# DevBit-ATmega328.net
KiCad netlist of a schematic drawn in EAGLE
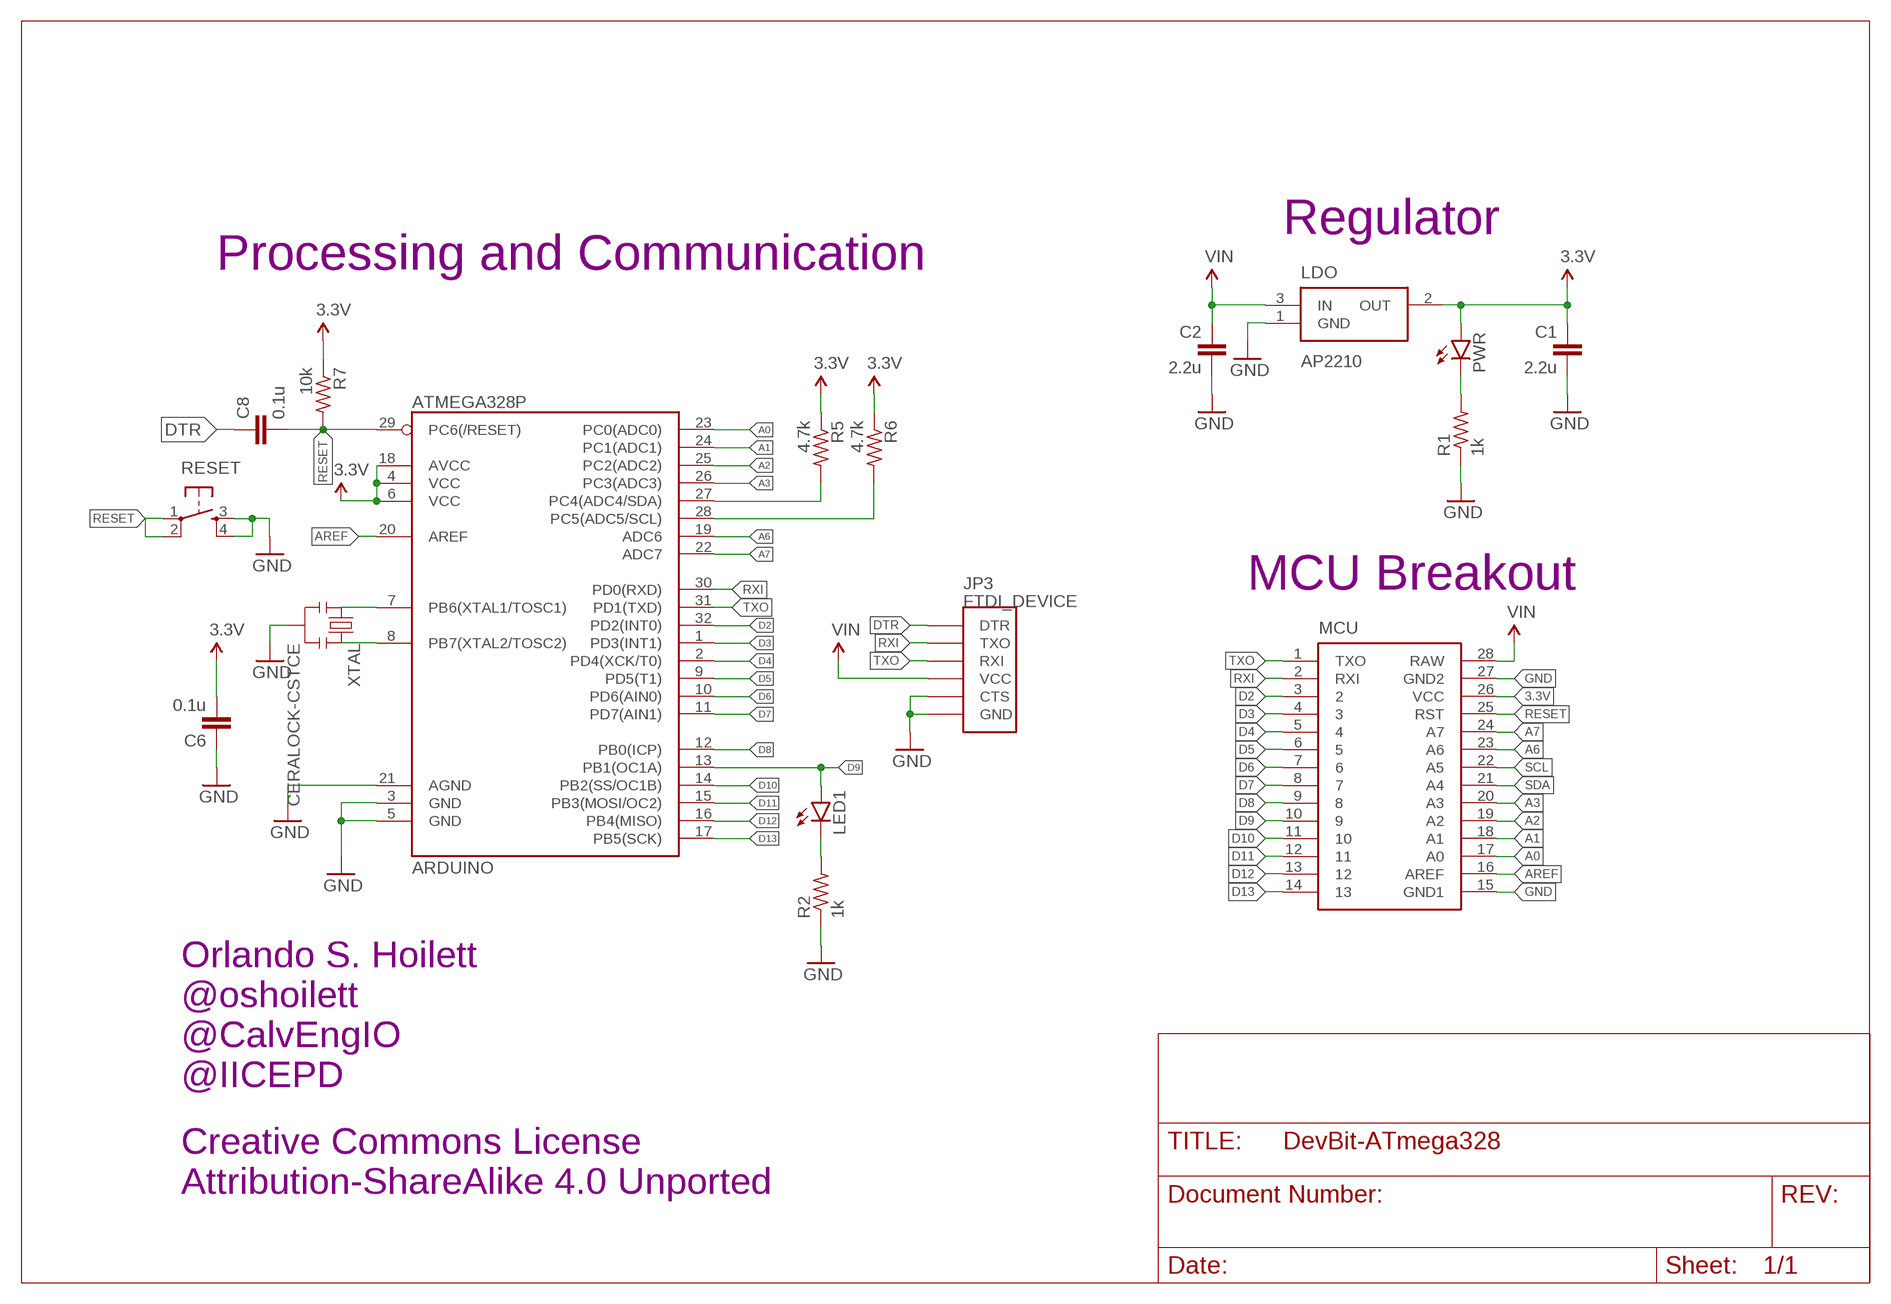
[diagram p0: schematic, sheet 1]

(export (version "E")
  (design (tool "Eeschema 10.0.6"))
  (components
    (comp (ref "ARDUINO")
      (value "ATMEGA328P")
      (footprint "eagle-import:TQFP32-08")
      (libsource (lib "eagle-import") (part "ATMEGA328_SMT-OHMOD"))
    )
    (comp (ref "C1")
      (value "2.2u")
      (footprint "eagle-import:C0402")
      (libsource (lib "eagle-import") (part "C-EUC0402"))
    )
    (comp (ref "C2")
      (value "2.2u")
      (footprint "eagle-import:C0402")
      (libsource (lib "eagle-import") (part "C-EUC0402"))
    )
    (comp (ref "C6")
      (value "0.1u")
      (footprint "eagle-import:C0402")
      (libsource (lib "eagle-import") (part "C-EUC0402"))
    )
    (comp (ref "C8")
      (value "0.1u")
      (footprint "eagle-import:C0402")
      (libsource (lib "eagle-import") (part "C-EUC0402"))
    )
    (comp (ref "JP3")
      (value "FTDI_DEVICE")
      (footprint "eagle-import:FTDI_DEVICE")
      (libsource (lib "eagle-import") (part "FTDI_DEVICE"))
    )
    (comp (ref "LDO")
      (value "AP2210")
      (footprint "eagle-import:SOT23")
      (libsource (lib "eagle-import") (part "AP2210"))
    )
    (comp (ref "LED1")
      (value "LED0603")
      (footprint "eagle-import:LED-0603")
      (libsource (lib "eagle-import") (part "LED0603"))
    )
    (comp (ref "MCU")
      (value "DEVBASIC-V1")
      (footprint "eagle-import:DEVBIT-BASIC-V1")
      (libsource (lib "eagle-import") (part "DEVBASIC-V1"))
    )
    (comp (ref "PWR")
      (value "LED0603")
      (footprint "eagle-import:LED-0603")
      (libsource (lib "eagle-import") (part "LED0603"))
    )
    (comp (ref "R1")
      (value "1k")
      (footprint "eagle-import:R0402")
      (libsource (lib "eagle-import") (part "R-US_R0402"))
    )
    (comp (ref "R2")
      (value "1k")
      (footprint "eagle-import:R0402")
      (libsource (lib "eagle-import") (part "R-US_R0402"))
    )
    (comp (ref "R5")
      (value "4.7k")
      (footprint "eagle-import:R0402")
      (libsource (lib "eagle-import") (part "R-US_R0402"))
    )
    (comp (ref "R6")
      (value "4.7k")
      (footprint "eagle-import:R0402")
      (libsource (lib "eagle-import") (part "R-US_R0402"))
    )
    (comp (ref "R7")
      (value "10k")
      (footprint "eagle-import:R0402")
      (libsource (lib "eagle-import") (part "R-US_R0402"))
    )
    (comp (ref "RESET")
      (value "BUTTON-PTS830GG140")
      (footprint "eagle-import:BUTTON-GULLWING")
      (libsource (lib "eagle-import") (part "BUTTON-PTS830GG140"))
    )
    (comp (ref "XTAL")
      (value "CERALOCK-CSTCE")
      (footprint "eagle-import:RESONATOR-00")
      (libsource (lib "eagle-import") (part "CERALOCK-CSTCE"))
    )
  )
  (nets
    (net (code "1") (name "3.3V") (class "Default")
      (node (ref "ARDUINO") (pin "18") (pinfunction "AVCC_18") (pintype "bidirectional"))
      (node (ref "ARDUINO") (pin "4") (pinfunction "VCC_4") (pintype "bidirectional"))
      (node (ref "ARDUINO") (pin "6") (pinfunction "VCC_6") (pintype "bidirectional"))
      (node (ref "C1") (pin "1") (pinfunction "1_1") (pintype "passive"))
      (node (ref "C6") (pin "2") (pinfunction "2_2") (pintype "passive"))
      (node (ref "LDO") (pin "2") (pinfunction "OUT_2") (pintype "bidirectional"))
      (node (ref "MCU") (pin "26") (pinfunction "VCC_26") (pintype "bidirectional"))
      (node (ref "PWR") (pin "A") (pinfunction "A_A") (pintype "passive"))
      (node (ref "R5") (pin "1") (pinfunction "1_1") (pintype "passive"))
      (node (ref "R6") (pin "1") (pinfunction "1_1") (pintype "passive"))
      (node (ref "R7") (pin "1") (pinfunction "1_1") (pintype "passive"))
    )
    (net (code "2") (name "A0") (class "Default")
      (node (ref "ARDUINO") (pin "23") (pinfunction "PC0(ADC0)_23") (pintype "bidirectional"))
      (node (ref "MCU") (pin "17") (pinfunction "A0_17") (pintype "bidirectional"))
    )
    (net (code "3") (name "A1") (class "Default")
      (node (ref "ARDUINO") (pin "24") (pinfunction "PC1(ADC1)_24") (pintype "bidirectional"))
      (node (ref "MCU") (pin "18") (pinfunction "A1_18") (pintype "bidirectional"))
    )
    (net (code "4") (name "A2") (class "Default")
      (node (ref "ARDUINO") (pin "25") (pinfunction "PC2(ADC2)_25") (pintype "bidirectional"))
      (node (ref "MCU") (pin "19") (pinfunction "A2_19") (pintype "bidirectional"))
    )
    (net (code "5") (name "A3") (class "Default")
      (node (ref "ARDUINO") (pin "26") (pinfunction "PC3(ADC3)_26") (pintype "bidirectional"))
      (node (ref "MCU") (pin "20") (pinfunction "A3_20") (pintype "bidirectional"))
    )
    (net (code "6") (name "A6") (class "Default")
      (node (ref "ARDUINO") (pin "19") (pinfunction "ADC6_19") (pintype "bidirectional"))
      (node (ref "MCU") (pin "23") (pinfunction "A6_23") (pintype "bidirectional"))
    )
    (net (code "7") (name "A7") (class "Default")
      (node (ref "ARDUINO") (pin "22") (pinfunction "ADC7_22") (pintype "bidirectional"))
      (node (ref "MCU") (pin "24") (pinfunction "A7_24") (pintype "bidirectional"))
    )
    (net (code "8") (name "AREF") (class "Default")
      (node (ref "ARDUINO") (pin "20") (pinfunction "AREF_20") (pintype "bidirectional"))
      (node (ref "MCU") (pin "16") (pinfunction "AREF_16") (pintype "bidirectional"))
    )
    (net (code "9") (name "D2") (class "Default")
      (node (ref "ARDUINO") (pin "32") (pinfunction "PD2(INT0)_32") (pintype "bidirectional"))
      (node (ref "MCU") (pin "3") (pinfunction "2_3") (pintype "bidirectional"))
    )
    (net (code "10") (name "D3") (class "Default")
      (node (ref "ARDUINO") (pin "1") (pinfunction "PD3(INT1)_1") (pintype "bidirectional"))
      (node (ref "MCU") (pin "4") (pinfunction "3_4") (pintype "bidirectional"))
    )
    (net (code "11") (name "D4") (class "Default")
      (node (ref "ARDUINO") (pin "2") (pinfunction "PD4(XCK/T0)_2") (pintype "bidirectional"))
      (node (ref "MCU") (pin "5") (pinfunction "4_5") (pintype "bidirectional"))
    )
    (net (code "12") (name "D5") (class "Default")
      (node (ref "ARDUINO") (pin "9") (pinfunction "PD5(T1)_9") (pintype "bidirectional"))
      (node (ref "MCU") (pin "6") (pinfunction "5_6") (pintype "bidirectional"))
    )
    (net (code "13") (name "D6") (class "Default")
      (node (ref "ARDUINO") (pin "10") (pinfunction "PD6(AIN0)_10") (pintype "bidirectional"))
      (node (ref "MCU") (pin "7") (pinfunction "6_7") (pintype "bidirectional"))
    )
    (net (code "14") (name "D7") (class "Default")
      (node (ref "ARDUINO") (pin "11") (pinfunction "PD7(AIN1)_11") (pintype "bidirectional"))
      (node (ref "MCU") (pin "8") (pinfunction "7_8") (pintype "bidirectional"))
    )
    (net (code "15") (name "D8") (class "Default")
      (node (ref "ARDUINO") (pin "12") (pinfunction "PB0(ICP)_12") (pintype "bidirectional"))
      (node (ref "MCU") (pin "9") (pinfunction "8_9") (pintype "bidirectional"))
    )
    (net (code "16") (name "D9") (class "Default")
      (node (ref "ARDUINO") (pin "13") (pinfunction "PB1(OC1A)_13") (pintype "bidirectional"))
      (node (ref "LED1") (pin "A") (pinfunction "A_A") (pintype "passive"))
      (node (ref "MCU") (pin "10") (pinfunction "9_10") (pintype "bidirectional"))
    )
    (net (code "17") (name "D10") (class "Default")
      (node (ref "ARDUINO") (pin "14") (pinfunction "PB2(SS/OC1B)_14") (pintype "bidirectional"))
      (node (ref "MCU") (pin "11") (pinfunction "10_11") (pintype "bidirectional"))
    )
    (net (code "18") (name "D11") (class "Default")
      (node (ref "ARDUINO") (pin "15") (pinfunction "PB3(MOSI/OC2)_15") (pintype "bidirectional"))
      (node (ref "MCU") (pin "12") (pinfunction "11_12") (pintype "bidirectional"))
    )
    (net (code "19") (name "D12") (class "Default")
      (node (ref "ARDUINO") (pin "16") (pinfunction "PB4(MISO)_16") (pintype "bidirectional"))
      (node (ref "MCU") (pin "13") (pinfunction "12_13") (pintype "bidirectional"))
    )
    (net (code "20") (name "D13") (class "Default")
      (node (ref "ARDUINO") (pin "17") (pinfunction "PB5(SCK)_17") (pintype "bidirectional"))
      (node (ref "MCU") (pin "14") (pinfunction "13_14") (pintype "bidirectional"))
    )
    (net (code "21") (name "DTR") (class "Default")
      (node (ref "C8") (pin "1") (pinfunction "1_1") (pintype "passive"))
      (node (ref "JP3") (pin "DTR") (pinfunction "DTR_DTR") (pintype "bidirectional"))
    )
    (net (code "22") (name "GND") (class "Default")
      (node (ref "ARDUINO") (pin "21") (pinfunction "AGND_21") (pintype "bidirectional"))
      (node (ref "ARDUINO") (pin "3") (pinfunction "GND_3") (pintype "bidirectional"))
      (node (ref "ARDUINO") (pin "5") (pinfunction "GND_5") (pintype "bidirectional"))
      (node (ref "C1") (pin "2") (pinfunction "2_2") (pintype "passive"))
      (node (ref "C2") (pin "2") (pinfunction "2_2") (pintype "passive"))
      (node (ref "C6") (pin "1") (pinfunction "1_1") (pintype "passive"))
      (node (ref "JP3") (pin "CTS") (pinfunction "CTS_CTS") (pintype "bidirectional"))
      (node (ref "JP3") (pin "GND") (pinfunction "GND_GND") (pintype "bidirectional"))
      (node (ref "LDO") (pin "1") (pinfunction "GND_1") (pintype "bidirectional"))
      (node (ref "MCU") (pin "15") (pinfunction "GND1_15") (pintype "bidirectional"))
      (node (ref "MCU") (pin "27") (pinfunction "GND2_27") (pintype "bidirectional"))
      (node (ref "R1") (pin "1") (pinfunction "1_1") (pintype "passive"))
      (node (ref "R2") (pin "1") (pinfunction "1_1") (pintype "passive"))
      (node (ref "RESET") (pin "3") (pinfunction "3_3") (pintype "passive"))
      (node (ref "RESET") (pin "4") (pinfunction "4_4") (pintype "passive"))
      (node (ref "XTAL") (pin "2") (pinfunction "2_2") (pintype "passive"))
    )
    (net (code "23") (name "Net-(ARDUINO-PB6(XTAL1{slash}TOSC1))") (class "Default")
      (node (ref "ARDUINO") (pin "7") (pinfunction "PB6(XTAL1/TOSC1)_7") (pintype "bidirectional"))
      (node (ref "XTAL") (pin "1") (pinfunction "1_1") (pintype "passive"))
    )
    (net (code "24") (name "Net-(ARDUINO-PB7(XTAL2{slash}TOSC2))") (class "Default")
      (node (ref "ARDUINO") (pin "8") (pinfunction "PB7(XTAL2/TOSC2)_8") (pintype "bidirectional"))
      (node (ref "XTAL") (pin "3") (pinfunction "3_3") (pintype "passive"))
    )
    (net (code "25") (name "Net-(LED1-PadC)") (class "Default")
      (node (ref "LED1") (pin "C") (pinfunction "C_C") (pintype "passive"))
      (node (ref "R2") (pin "2") (pinfunction "2_2") (pintype "passive"))
    )
    (net (code "26") (name "Net-(PWR-PadC)") (class "Default")
      (node (ref "PWR") (pin "C") (pinfunction "C_C") (pintype "passive"))
      (node (ref "R1") (pin "2") (pinfunction "2_2") (pintype "passive"))
    )
    (net (code "27") (name "RESET") (class "Default")
      (node (ref "ARDUINO") (pin "29") (pinfunction "PC6(/RESET)_29") (pintype "bidirectional"))
      (node (ref "C8") (pin "2") (pinfunction "2_2") (pintype "passive"))
      (node (ref "MCU") (pin "25") (pinfunction "RST_25") (pintype "bidirectional"))
      (node (ref "R7") (pin "2") (pinfunction "2_2") (pintype "passive"))
      (node (ref "RESET") (pin "1") (pinfunction "1_1") (pintype "passive"))
      (node (ref "RESET") (pin "2") (pinfunction "2_2") (pintype "passive"))
    )
    (net (code "28") (name "RXI") (class "Default")
      (node (ref "ARDUINO") (pin "30") (pinfunction "PD0(RXD)_30") (pintype "bidirectional"))
      (node (ref "JP3") (pin "TXO") (pinfunction "TXO_TXO") (pintype "bidirectional"))
      (node (ref "MCU") (pin "2") (pinfunction "RXI_2") (pintype "bidirectional"))
    )
    (net (code "29") (name "SCL") (class "Default")
      (node (ref "ARDUINO") (pin "28") (pinfunction "PC5(ADC5/SCL)_28") (pintype "bidirectional"))
      (node (ref "MCU") (pin "22") (pinfunction "A5_22") (pintype "bidirectional"))
      (node (ref "R6") (pin "2") (pinfunction "2_2") (pintype "passive"))
    )
    (net (code "30") (name "SDA") (class "Default")
      (node (ref "ARDUINO") (pin "27") (pinfunction "PC4(ADC4/SDA)_27") (pintype "bidirectional"))
      (node (ref "MCU") (pin "21") (pinfunction "A4_21") (pintype "bidirectional"))
      (node (ref "R5") (pin "2") (pinfunction "2_2") (pintype "passive"))
    )
    (net (code "31") (name "TXO") (class "Default")
      (node (ref "ARDUINO") (pin "31") (pinfunction "PD1(TXD)_31") (pintype "bidirectional"))
      (node (ref "JP3") (pin "RXI") (pinfunction "RXI_RXI") (pintype "bidirectional"))
      (node (ref "MCU") (pin "1") (pinfunction "TXO_1") (pintype "bidirectional"))
    )
    (net (code "32") (name "VIN") (class "Default")
      (node (ref "C2") (pin "1") (pinfunction "1_1") (pintype "passive"))
      (node (ref "JP3") (pin "VCC") (pinfunction "VCC_VCC") (pintype "bidirectional"))
      (node (ref "LDO") (pin "3") (pinfunction "IN_3") (pintype "bidirectional"))
      (node (ref "MCU") (pin "28") (pinfunction "RAW_28") (pintype "bidirectional"))
    )
  )
)
